# STM.net
KiCad netlist of a schematic drawn in Altium Designer
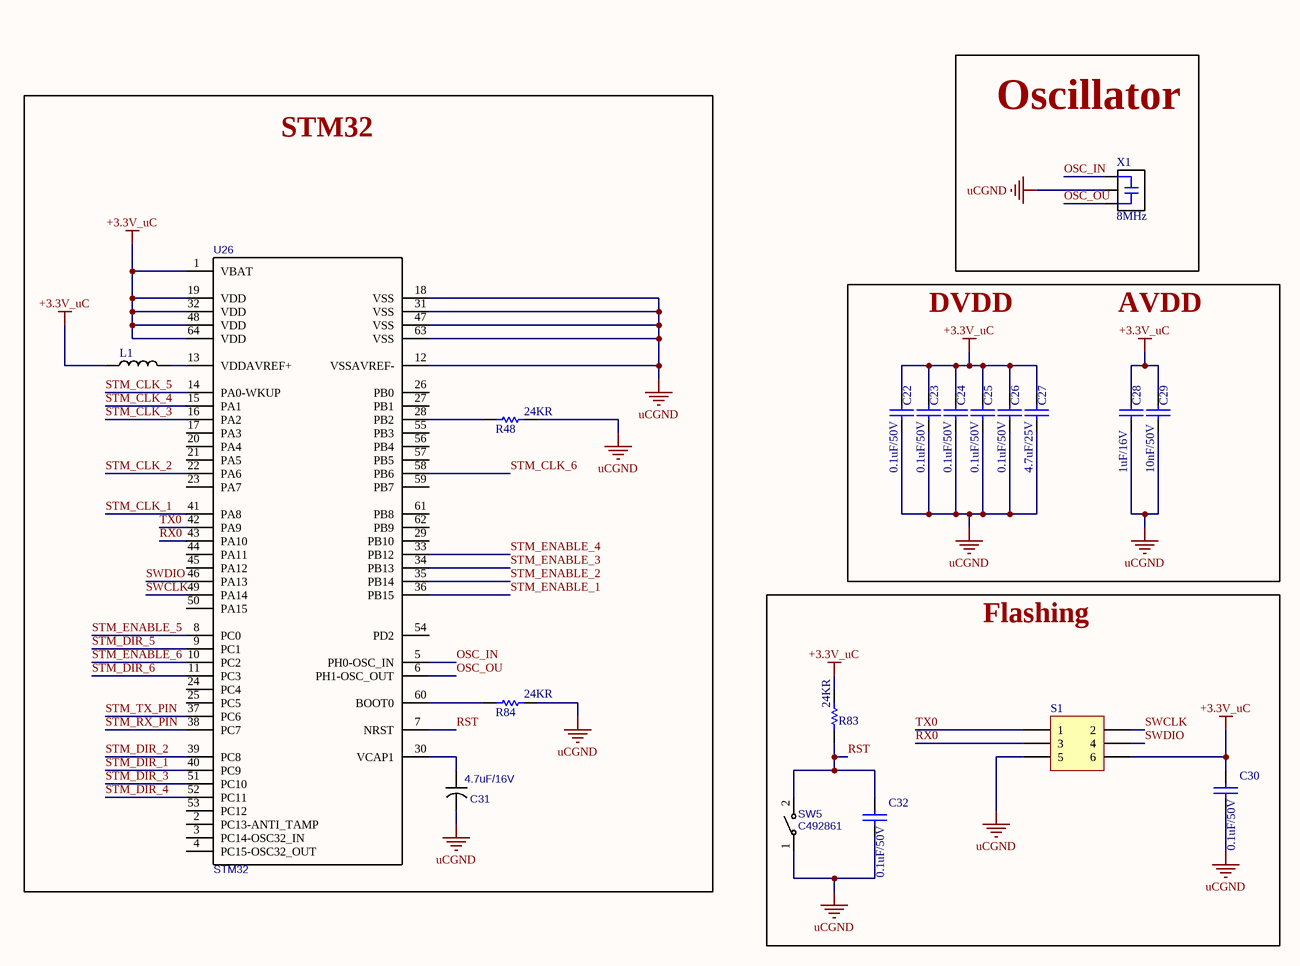
[diagram p0: STM.SchDoc]

(export (version "E")
  (design (tool "Eeschema 10.0.6"))
  (components
    (comp (ref "C22")
      (value "0.1uF/50V")
      (footprint "PCBComponent_1")
      (description "C1591")
      (fields (field (name "CREATED BY") "NourAldin"))
      (libsource (lib "0603 Capacitor") (part "0603 Capacitor"))
    )
    (comp (ref "C23")
      (value "0.1uF/50V")
      (footprint "PCBComponent_1")
      (description "C1591")
      (fields (field (name "CREATED BY") "NourAldin"))
      (libsource (lib "0603 Capacitor") (part "0603 Capacitor"))
    )
    (comp (ref "C24")
      (value "0.1uF/50V")
      (footprint "PCBComponent_1")
      (description "C1591")
      (fields (field (name "CREATED BY") "NourAldin"))
      (libsource (lib "0603 Capacitor") (part "0603 Capacitor"))
    )
    (comp (ref "C25")
      (value "0.1uF/50V")
      (footprint "PCBComponent_1")
      (description "C1591")
      (fields (field (name "CREATED BY") "NourAldin"))
      (libsource (lib "0603 Capacitor") (part "0603 Capacitor"))
    )
    (comp (ref "C26")
      (value "0.1uF/50V")
      (footprint "PCBComponent_1")
      (description "C1591")
      (fields (field (name "CREATED BY") "NourAldin"))
      (libsource (lib "0603 Capacitor") (part "0603 Capacitor"))
    )
    (comp (ref "C27")
      (value "4.7uF/25V")
      (footprint "PCBComponent_1")
      (description "C69335")
      (fields (field (name "CREATED BY") "NourAldin"))
      (libsource (lib "0603 Capacitor") (part "0603 Capacitor"))
    )
    (comp (ref "C28")
      (value "1uF/16V")
      (footprint "PCBComponent_1")
      (description "C1592")
      (fields (field (name "CREATED BY") "NourAldin"))
      (libsource (lib "0603 Capacitor") (part "0603 Capacitor"))
    )
    (comp (ref "C29")
      (value "10nF/50V")
      (footprint "PCBComponent_1")
      (description "C100042")
      (fields (field (name "CREATED BY") "NourAldin"))
      (libsource (lib "0603 Capacitor") (part "0603 Capacitor"))
    )
    (comp (ref "C30")
      (value "0.1uF/50V")
      (footprint "PCBComponent_1")
      (description "C1591")
      (fields (field (name "CREATED BY") "NourAldin"))
      (libsource (lib "0603 Capacitor") (part "0603 Capacitor"))
    )
    (comp (ref "C31")
      (value "4.7uF/16V")
      (footprint "CASE-B_3528")
      (description "C7206")
      (fields
        (field (name "MANUFACTURER") "Kyocera AVX")
        (field (name "MANUFACTURER PART") "TAJR106K006RNJ")
        (field (name "CONTRIBUTOR") "LCSC")
      )
      (libsource (lib "DIVERSE") (part "3528  Tantalum Cap"))
    )
    (comp (ref "C32")
      (value "0.1uF/50V")
      (footprint "PCBComponent_1")
      (description "C1591")
      (fields (field (name "CREATED BY") "NourAldin"))
      (libsource (lib "0603 Capacitor") (part "0603 Capacitor"))
    )
    (comp (ref "L1")
      (value "CMI201209X100KT")
      (footprint "INDC2012X06N")
      (description "C99366")
      (fields (field (name "CREATED BY") "NourAldin"))
      (libsource (lib "0805 Inductor") (part "0805 SMD INDUCTOR"))
    )
    (comp (ref "R48")
      (value "24KR")
      (footprint "RESC1608X06N")
      (description "C2930081")
      (fields (field (name "CREATED BY") "NourAldin"))
      (libsource (lib "0603 Resistor") (part "0603 Resistor"))
    )
    (comp (ref "R83")
      (value "24KR")
      (footprint "RESC1608X06N")
      (description "C2930081")
      (fields (field (name "CREATED BY") "NourAldin"))
      (libsource (lib "0603 Resistor") (part "0603 Resistor"))
    )
    (comp (ref "R84")
      (value "24KR")
      (footprint "RESC1608X06N")
      (description "C2930081")
      (fields (field (name "CREATED BY") "NourAldin"))
      (libsource (lib "0603 Resistor") (part "0603 Resistor"))
    )
    (comp (ref "S1")
      (value "Header 3X2")
      (footprint "HDR2X3")
      (description "C42431837")
      (fields (field (name "PUBLISHER") "Altium Limited"))
      (libsource (lib "Miscellaneous Connectors") (part "Header 3X2"))
    )
    (comp (ref "SW5")
      (value "C492861")
      (footprint "SW-SMD_L4.0-W3.0-LS4.8")
      (fields
        (field (name "MANUFACTURER") "Yuandi(元迪)")
        (field (name "MANUFACTURER PART") "TS-1071AS-A1B3-D4")
        (field (name "CONTRIBUTOR") "LCSC")
      )
      (libsource (lib "DIVERSE") (part "tact switch"))
    )
    (comp (ref "U26")
      (value "STM32")
      (footprint "LQFP-64_L10.0-W10.0-P0.50-LS12.0-BL")
      (description "C74524")
      (fields (field (name "MANUFACTURER") "ST(意法半导体)") (field (name "MANUFACTURER PART") "STM32F401RCT6"))
      (libsource (lib "DIVERSE") (part "STM32F401RCT6"))
    )
    (comp (ref "X1")
      (value "8MHz")
      (footprint "SMD3213-3P")
      (description "C907975")
      (fields
        (field (name "MANUFACTURER") "Murata")
        (field (name "MANUFACTURER PART NUMBER") "CSTCE16M0V53-R0")
      )
      (libsource (lib "CO2_Lib") (part "CSTCE16M0V53-R0"))
    )
  )
  (nets
    (net (code "1") (name "+3.3V_uC") (class "Default")
      (node (ref "C22") (pin "2") (pinfunction "2_2") (pintype "passive"))
      (node (ref "C23") (pin "2") (pinfunction "2_2") (pintype "passive"))
      (node (ref "C24") (pin "2") (pinfunction "2_2") (pintype "passive"))
      (node (ref "C25") (pin "2") (pinfunction "2_2") (pintype "passive"))
      (node (ref "C26") (pin "2") (pinfunction "2_2") (pintype "passive"))
      (node (ref "C27") (pin "2") (pinfunction "2_2") (pintype "passive"))
      (node (ref "C28") (pin "2") (pinfunction "2_2") (pintype "passive"))
      (node (ref "C29") (pin "2") (pinfunction "2_2") (pintype "passive"))
      (node (ref "C30") (pin "2") (pinfunction "2_2") (pintype "passive"))
      (node (ref "L1") (pin "1") (pinfunction "1_1") (pintype "passive"))
      (node (ref "R83") (pin "1") (pinfunction "1_1") (pintype "passive"))
      (node (ref "S1") (pin "6") (pinfunction "6_6") (pintype "passive"))
      (node (ref "U26") (pin "1") (pinfunction "VBAT_1") (pintype "passive"))
      (node (ref "U26") (pin "19") (pinfunction "VDD_19") (pintype "passive"))
      (node (ref "U26") (pin "32") (pinfunction "VDD_32") (pintype "passive"))
      (node (ref "U26") (pin "48") (pinfunction "VDD_48") (pintype "passive"))
      (node (ref "U26") (pin "64") (pinfunction "VDD_64") (pintype "passive"))
    )
    (net (code "2") (name "/OSC_IN") (class "Default")
      (node (ref "U26") (pin "5") (pinfunction "PH0-OSC_IN_5") (pintype "passive"))
      (node (ref "X1") (pin "1") (pinfunction "1_1") (pintype "passive"))
    )
    (net (code "3") (name "/OSC_OU") (class "Default")
      (node (ref "U26") (pin "6") (pinfunction "PH1-OSC_OUT_6") (pintype "passive"))
      (node (ref "X1") (pin "3") (pinfunction "3_3") (pintype "passive"))
    )
    (net (code "4") (name "/RST") (class "Default")
      (node (ref "C32") (pin "2") (pinfunction "2_2") (pintype "passive"))
      (node (ref "R83") (pin "2") (pinfunction "2_2") (pintype "passive"))
      (node (ref "SW5") (pin "2") (pinfunction "2_2") (pintype "passive"))
      (node (ref "U26") (pin "7") (pinfunction "NRST_7") (pintype "passive"))
    )
    (net (code "5") (name "/RX0") (class "Default")
      (node (ref "S1") (pin "3") (pinfunction "3_3") (pintype "passive"))
      (node (ref "U26") (pin "43") (pinfunction "PA10_43") (pintype "passive"))
    )
    (net (code "6") (name "/STM_CLK_1") (class "Default")
      (node (ref "U26") (pin "41") (pinfunction "PA8_41") (pintype "passive"))
    )
    (net (code "7") (name "/STM_CLK_2") (class "Default")
      (node (ref "U26") (pin "22") (pinfunction "PA6_22") (pintype "passive"))
    )
    (net (code "8") (name "/STM_CLK_3") (class "Default")
      (node (ref "U26") (pin "16") (pinfunction "PA2_16") (pintype "passive"))
    )
    (net (code "9") (name "/STM_CLK_4") (class "Default")
      (node (ref "U26") (pin "15") (pinfunction "PA1_15") (pintype "passive"))
    )
    (net (code "10") (name "/STM_CLK_5") (class "Default")
      (node (ref "U26") (pin "14") (pinfunction "PA0-WKUP_14") (pintype "passive"))
    )
    (net (code "11") (name "/STM_CLK_6") (class "Default")
      (node (ref "U26") (pin "58") (pinfunction "PB6_58") (pintype "passive"))
    )
    (net (code "12") (name "/STM_DIR_1") (class "Default")
      (node (ref "U26") (pin "40") (pinfunction "PC9_40") (pintype "passive"))
    )
    (net (code "13") (name "/STM_DIR_2") (class "Default")
      (node (ref "U26") (pin "39") (pinfunction "PC8_39") (pintype "passive"))
    )
    (net (code "14") (name "/STM_DIR_3") (class "Default")
      (node (ref "U26") (pin "51") (pinfunction "PC10_51") (pintype "passive"))
    )
    (net (code "15") (name "/STM_DIR_4") (class "Default")
      (node (ref "U26") (pin "52") (pinfunction "PC11_52") (pintype "passive"))
    )
    (net (code "16") (name "/STM_DIR_5") (class "Default")
      (node (ref "U26") (pin "9") (pinfunction "PC1_9") (pintype "passive"))
    )
    (net (code "17") (name "/STM_DIR_6") (class "Default")
      (node (ref "U26") (pin "11") (pinfunction "PC3_11") (pintype "passive"))
    )
    (net (code "18") (name "/STM_ENABLE_1") (class "Default")
      (node (ref "U26") (pin "36") (pinfunction "PB15_36") (pintype "passive"))
    )
    (net (code "19") (name "/STM_ENABLE_2") (class "Default")
      (node (ref "U26") (pin "35") (pinfunction "PB14_35") (pintype "passive"))
    )
    (net (code "20") (name "/STM_ENABLE_3") (class "Default")
      (node (ref "U26") (pin "34") (pinfunction "PB13_34") (pintype "passive"))
    )
    (net (code "21") (name "/STM_ENABLE_4") (class "Default")
      (node (ref "U26") (pin "33") (pinfunction "PB12_33") (pintype "passive"))
    )
    (net (code "22") (name "/STM_ENABLE_5") (class "Default")
      (node (ref "U26") (pin "8") (pinfunction "PC0_8") (pintype "passive"))
    )
    (net (code "23") (name "/STM_ENABLE_6") (class "Default")
      (node (ref "U26") (pin "10") (pinfunction "PC2_10") (pintype "passive"))
    )
    (net (code "24") (name "/STM_RX_PIN") (class "Default")
      (node (ref "U26") (pin "38") (pinfunction "PC7_38") (pintype "passive"))
    )
    (net (code "25") (name "/STM_TX_PIN") (class "Default")
      (node (ref "U26") (pin "37") (pinfunction "PC6_37") (pintype "passive"))
    )
    (net (code "26") (name "/SWCLK") (class "Default")
      (node (ref "S1") (pin "2") (pinfunction "2_2") (pintype "passive"))
      (node (ref "U26") (pin "49") (pinfunction "PA14_49") (pintype "passive"))
    )
    (net (code "27") (name "/SWDIO") (class "Default")
      (node (ref "S1") (pin "4") (pinfunction "4_4") (pintype "passive"))
      (node (ref "U26") (pin "46") (pinfunction "PA13_46") (pintype "passive"))
    )
    (net (code "28") (name "/TX0") (class "Default")
      (node (ref "S1") (pin "1") (pinfunction "1_1") (pintype "passive"))
      (node (ref "U26") (pin "42") (pinfunction "PA9_42") (pintype "passive"))
    )
    (net (code "29") (name "Net-(U26-BOOT0)") (class "Default")
      (node (ref "R84") (pin "2") (pinfunction "2_2") (pintype "passive"))
      (node (ref "U26") (pin "60") (pinfunction "BOOT0_60") (pintype "passive"))
    )
    (net (code "30") (name "Net-(U26-PB2)") (class "Default")
      (node (ref "R48") (pin "2") (pinfunction "2_2") (pintype "passive"))
      (node (ref "U26") (pin "28") (pinfunction "PB2_28") (pintype "passive"))
    )
    (net (code "31") (name "Net-(U26-VCAP1)") (class "Default")
      (node (ref "C31") (pin "1") (pinfunction "1_1") (pintype "passive"))
      (node (ref "U26") (pin "30") (pinfunction "VCAP1_30") (pintype "passive"))
    )
    (net (code "32") (name "Net-(U26-VDDAVREF+)") (class "Default")
      (node (ref "L1") (pin "2") (pinfunction "2_2") (pintype "passive"))
      (node (ref "U26") (pin "13") (pinfunction "VDDAVREF+_13") (pintype "passive"))
    )
    (net (code "33") (name "uCGND") (class "Default")
      (node (ref "C22") (pin "1") (pinfunction "1_1") (pintype "passive"))
      (node (ref "C23") (pin "1") (pinfunction "1_1") (pintype "passive"))
      (node (ref "C24") (pin "1") (pinfunction "1_1") (pintype "passive"))
      (node (ref "C25") (pin "1") (pinfunction "1_1") (pintype "passive"))
      (node (ref "C26") (pin "1") (pinfunction "1_1") (pintype "passive"))
      (node (ref "C27") (pin "1") (pinfunction "1_1") (pintype "passive"))
      (node (ref "C28") (pin "1") (pinfunction "1_1") (pintype "passive"))
      (node (ref "C29") (pin "1") (pinfunction "1_1") (pintype "passive"))
      (node (ref "C30") (pin "1") (pinfunction "1_1") (pintype "passive"))
      (node (ref "C31") (pin "2") (pinfunction "2_2") (pintype "passive"))
      (node (ref "C32") (pin "1") (pinfunction "1_1") (pintype "passive"))
      (node (ref "R48") (pin "1") (pinfunction "1_1") (pintype "passive"))
      (node (ref "R84") (pin "1") (pinfunction "1_1") (pintype "passive"))
      (node (ref "S1") (pin "5") (pinfunction "5_5") (pintype "passive"))
      (node (ref "SW5") (pin "1") (pinfunction "1_1") (pintype "passive"))
      (node (ref "U26") (pin "12") (pinfunction "VSSAVREF-_12") (pintype "passive"))
      (node (ref "U26") (pin "18") (pinfunction "VSS_18") (pintype "passive"))
      (node (ref "U26") (pin "31") (pinfunction "VSS_31") (pintype "passive"))
      (node (ref "U26") (pin "47") (pinfunction "VSS_47") (pintype "passive"))
      (node (ref "U26") (pin "63") (pinfunction "VSS_63") (pintype "passive"))
      (node (ref "X1") (pin "2") (pinfunction "2_2") (pintype "passive"))
    )
    (net (code "34") (name "unconnected-(U26-PA3-Pad17)") (class "Default")
      (node (ref "U26") (pin "17") (pinfunction "PA3_17") (pintype "passive"))
    )
    (net (code "35") (name "unconnected-(U26-PA4-Pad20)") (class "Default")
      (node (ref "U26") (pin "20") (pinfunction "PA4_20") (pintype "passive"))
    )
    (net (code "36") (name "unconnected-(U26-PA5-Pad21)") (class "Default")
      (node (ref "U26") (pin "21") (pinfunction "PA5_21") (pintype "passive"))
    )
    (net (code "37") (name "unconnected-(U26-PA7-Pad23)") (class "Default")
      (node (ref "U26") (pin "23") (pinfunction "PA7_23") (pintype "passive"))
    )
    (net (code "38") (name "unconnected-(U26-PA11-Pad44)") (class "Default")
      (node (ref "U26") (pin "44") (pinfunction "PA11_44") (pintype "passive"))
    )
    (net (code "39") (name "unconnected-(U26-PA12-Pad45)") (class "Default")
      (node (ref "U26") (pin "45") (pinfunction "PA12_45") (pintype "passive"))
    )
    (net (code "40") (name "unconnected-(U26-PA15-Pad50)") (class "Default")
      (node (ref "U26") (pin "50") (pinfunction "PA15_50") (pintype "passive"))
    )
    (net (code "41") (name "unconnected-(U26-PB0-Pad26)") (class "Default")
      (node (ref "U26") (pin "26") (pinfunction "PB0_26") (pintype "passive"))
    )
    (net (code "42") (name "unconnected-(U26-PB1-Pad27)") (class "Default")
      (node (ref "U26") (pin "27") (pinfunction "PB1_27") (pintype "passive"))
    )
    (net (code "43") (name "unconnected-(U26-PB3-Pad55)") (class "Default")
      (node (ref "U26") (pin "55") (pinfunction "PB3_55") (pintype "passive"))
    )
    (net (code "44") (name "unconnected-(U26-PB4-Pad56)") (class "Default")
      (node (ref "U26") (pin "56") (pinfunction "PB4_56") (pintype "passive"))
    )
    (net (code "45") (name "unconnected-(U26-PB5-Pad57)") (class "Default")
      (node (ref "U26") (pin "57") (pinfunction "PB5_57") (pintype "passive"))
    )
    (net (code "46") (name "unconnected-(U26-PB7-Pad59)") (class "Default")
      (node (ref "U26") (pin "59") (pinfunction "PB7_59") (pintype "passive"))
    )
    (net (code "47") (name "unconnected-(U26-PB8-Pad61)") (class "Default")
      (node (ref "U26") (pin "61") (pinfunction "PB8_61") (pintype "passive"))
    )
    (net (code "48") (name "unconnected-(U26-PB9-Pad62)") (class "Default")
      (node (ref "U26") (pin "62") (pinfunction "PB9_62") (pintype "passive"))
    )
    (net (code "49") (name "unconnected-(U26-PB10-Pad29)") (class "Default")
      (node (ref "U26") (pin "29") (pinfunction "PB10_29") (pintype "passive"))
    )
    (net (code "50") (name "unconnected-(U26-PC4-Pad24)") (class "Default")
      (node (ref "U26") (pin "24") (pinfunction "PC4_24") (pintype "passive"))
    )
    (net (code "51") (name "unconnected-(U26-PC5-Pad25)") (class "Default")
      (node (ref "U26") (pin "25") (pinfunction "PC5_25") (pintype "passive"))
    )
    (net (code "52") (name "unconnected-(U26-PC12-Pad53)") (class "Default")
      (node (ref "U26") (pin "53") (pinfunction "PC12_53") (pintype "passive"))
    )
    (net (code "53") (name "unconnected-(U26-PC13-ANTI_TAMP-Pad2)") (class "Default")
      (node (ref "U26") (pin "2") (pinfunction "PC13-ANTI_TAMP_2") (pintype "passive"))
    )
    (net (code "54") (name "unconnected-(U26-PC14-OSC32_IN-Pad3)") (class "Default")
      (node (ref "U26") (pin "3") (pinfunction "PC14-OSC32_IN_3") (pintype "passive"))
    )
    (net (code "55") (name "unconnected-(U26-PC15-OSC32_OUT-Pad4)") (class "Default")
      (node (ref "U26") (pin "4") (pinfunction "PC15-OSC32_OUT_4") (pintype "passive"))
    )
    (net (code "56") (name "unconnected-(U26-PD2-Pad54)") (class "Default")
      (node (ref "U26") (pin "54") (pinfunction "PD2_54") (pintype "passive"))
    )
  )
)
